# STM32F103C8T6.net
KiCad netlist of a schematic drawn in EasyEDA Pro
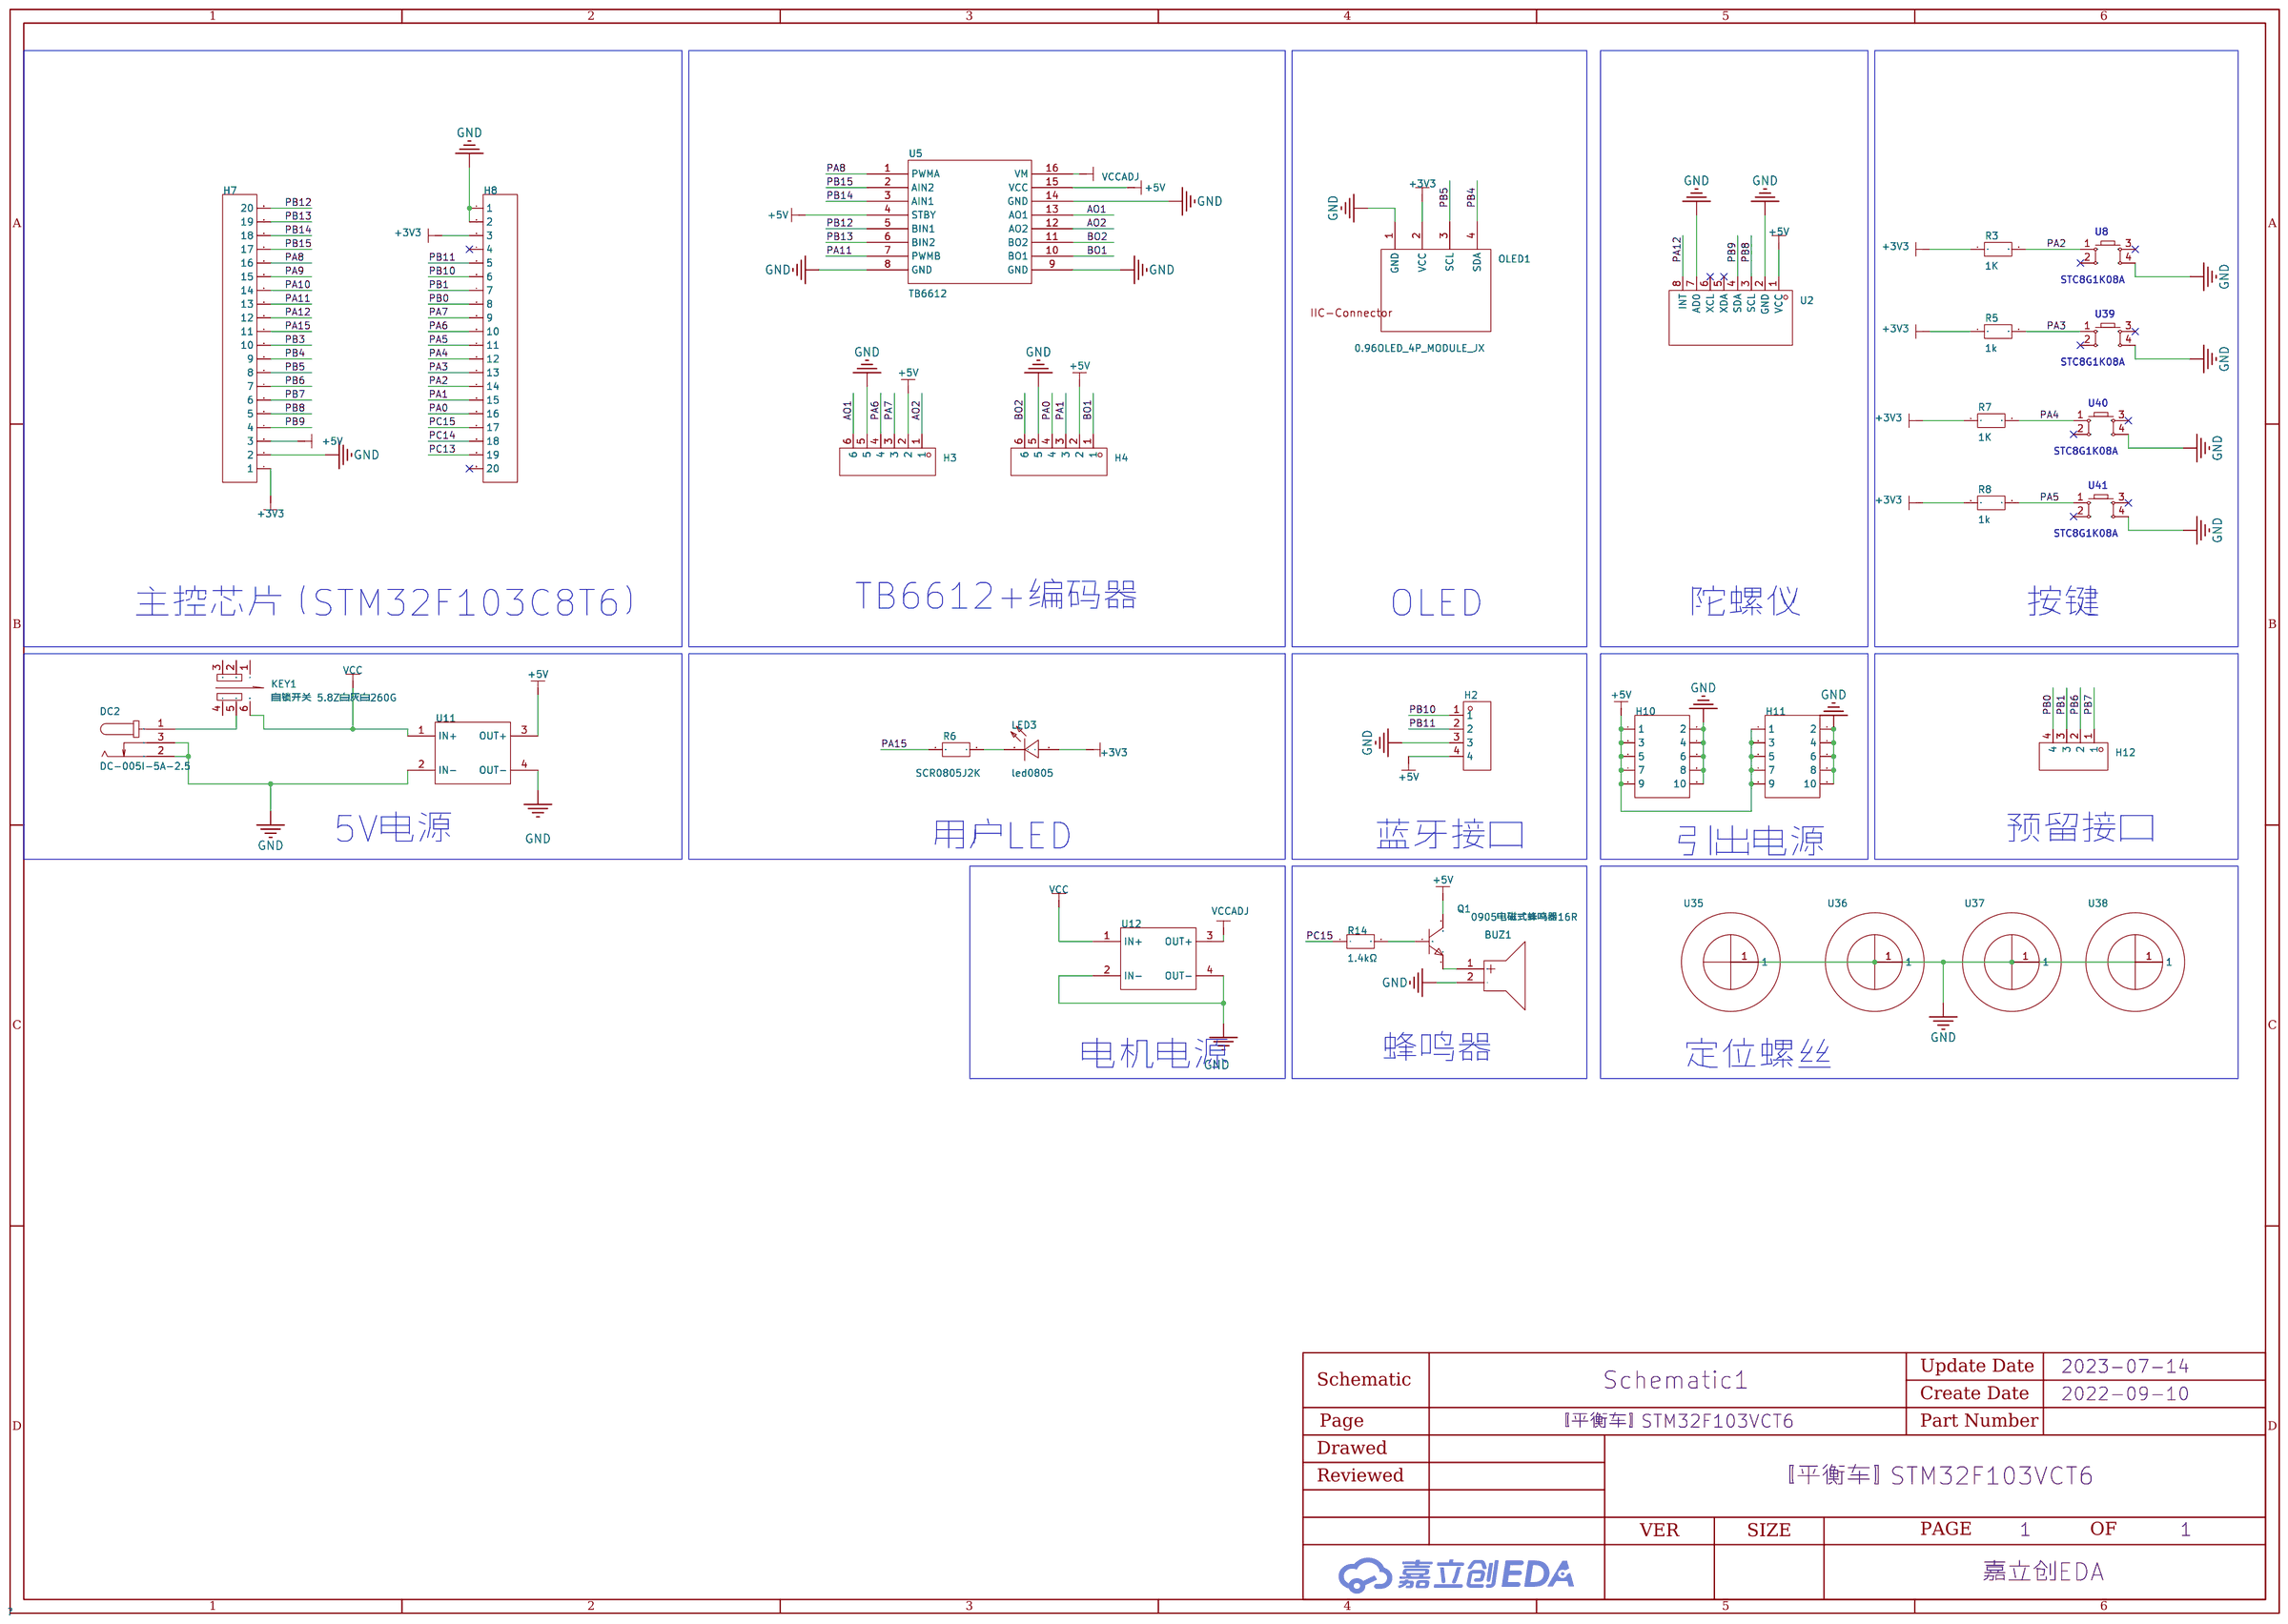
[diagram p0: schematic sheet]

(export (version "E")
  (design (tool "Eeschema 10.0.6"))
  (components
    (comp (ref "BUZ1")
      (value "0905电磁式蜂鸣器16R")
      (footprint "easyedapro:BUZ-TH_BD9.0-P4.00-D0.6-FD")
      (libsource (lib "easyedapro") (part "0905电磁式蜂鸣器16R"))
    )
    (comp (ref "DC2")
      (value "DC-005I-5A-2.5")
      (footprint "easyedapro:DC-IN-TH_DC-005I-5A-2.5")
      (fields (field (name "Manufacturer") "XKB Connectivity(中国星坤)"))
      (libsource (lib "easyedapro") (part "DC-005I-5A-2.5"))
    )
    (comp (ref "H2")
      (value "~")
      (footprint "easyedapro:HDR-TH_4P-P2.54-V-F")
      (libsource (lib "easyedapro") (part "2.54-1*4P母"))
    )
    (comp (ref "H3")
      (value "~")
      (footprint "easyedapro:HDR-TH_6P-P2.54-V-F")
      (libsource (lib "easyedapro") (part "Header-Female-2.54_1x6"))
    )
    (comp (ref "H4")
      (value "~")
      (footprint "easyedapro:HDR-TH_6P-P2.54-V-F")
      (libsource (lib "easyedapro") (part "Header-Female-2.54_1x6"))
    )
    (comp (ref "H7")
      (value "~")
      (footprint "easyedapro:HDR-TH_20P-P2.54-V-F")
      (libsource (lib "easyedapro") (part "HDR-F_2.54_1x20P"))
    )
    (comp (ref "H8")
      (value "~")
      (footprint "easyedapro:HDR-TH_20P-P2.54-V-F")
      (libsource (lib "easyedapro") (part "HDR-F_2.54_1x20P"))
    )
    (comp (ref "H10")
      (value "~")
      (footprint "easyedapro:HDR-TH_10P-P2.54-V-F-R2-C5-S2.54")
      (libsource (lib "easyedapro") (part "HDR-F-2.54_2x5"))
    )
    (comp (ref "H11")
      (value "~")
      (footprint "easyedapro:HDR-TH_10P-P2.54-V-F-R2-C5-S2.54")
      (libsource (lib "easyedapro") (part "HDR-F-2.54_2x5"))
    )
    (comp (ref "H12")
      (value "~")
      (footprint "easyedapro:HDR-TH_4P-P2.54-V-F")
      (libsource (lib "easyedapro") (part "2.54-1*4P母"))
    )
    (comp (ref "KEY1")
      (value "自锁开关 5.8Z白灰白260G")
      (footprint "easyedapro:SW-TH_6P-L5.8-W5.8-P2.00-LS4.5-TR")
      (description "耐温260度")
      (libsource (lib "easyedapro") (part "Self-locking switch 5.8ZWhite and white260G"))
    )
    (comp (ref "LED3")
      (value "led0805")
      (footprint "easyedapro:LED0805-RD")
      (libsource (lib "easyedapro") (part "LED0805"))
    )
    (comp (ref "OLED1")
      (value "0.96OLED_4P_MODULE_JX")
      (footprint "easyedapro:0.96OLED_4P")
      (libsource (lib "easyedapro") (part "0.96OLED_4P_MODULE_JX"))
    )
    (comp (ref "Q1")
      (value "~")
      (footprint "easyedapro:S8050_TO_92")
      (libsource (lib "easyedapro") (part "S8050_TO_NPN"))
    )
    (comp (ref "R3")
      (value "1K")
      (footprint "easyedapro:R0805")
      (fields (field (name "Manufacturer Part") "SCR0805J2K") (field (name "Manufacturer") "VO(翔胜)"))
      (libsource (lib "easyedapro") (part "SCR0805J2K"))
    )
    (comp (ref "R5")
      (value "1k")
      (footprint "easyedapro:R0805")
      (fields (field (name "Manufacturer Part") "SCR0805J2K") (field (name "Manufacturer") "VO(翔胜)"))
      (libsource (lib "easyedapro") (part "SCR0805J2K"))
    )
    (comp (ref "R6")
      (value "SCR0805J2K")
      (footprint "easyedapro:R0805")
      (fields (field (name "Manufacturer") "VO(翔胜)"))
      (libsource (lib "easyedapro") (part "SCR0805J2K"))
    )
    (comp (ref "R7")
      (value "1K")
      (footprint "easyedapro:R0805")
      (fields (field (name "Manufacturer Part") "SCR0805J2K") (field (name "Manufacturer") "VO(翔胜)"))
      (libsource (lib "easyedapro") (part "SCR0805J2K"))
    )
    (comp (ref "R8")
      (value "1k")
      (footprint "easyedapro:R0805")
      (fields (field (name "Manufacturer Part") "SCR0805J2K") (field (name "Manufacturer") "VO(翔胜)"))
      (libsource (lib "easyedapro") (part "SCR0805J2K"))
    )
    (comp (ref "R14")
      (value "1.4kΩ")
      (footprint "easyedapro:R0603")
      (description "电阻类型:厚膜电阻;阻值:1.4kΩ;精度:±1%;功率:100mW;")
      (fields
        (field (name "Manufacturer Part") "CRCW06031K40FKEA")
        (field (name "Manufacturer") "VISHAY(威世)")
      )
      (libsource (lib "easyedapro") (part "CRCW06031K40FKEA"))
    )
    (comp (ref "U2")
      (value "~")
      (footprint "easyedapro:MPU6050")
      (libsource (lib "easyedapro") (part "MPU6050"))
    )
    (comp (ref "U5")
      (value "TB6612")
      (footprint "easyedapro:TB6612")
      (libsource (lib "easyedapro") (part "TB6612"))
    )
    (comp (ref "U8")
      (value "STC8G1K08A")
      (footprint "easyedapro:SW-TH_4P-L6.0-W6.0-P4.50-LS6.5")
      (libsource (lib "easyedapro") (part "轻触按键直插"))
    )
    (comp (ref "U11")
      (value "~")
      (footprint "easyedapro:LM2596模块")
      (libsource (lib "easyedapro") (part "LM2596模块"))
    )
    (comp (ref "U12")
      (value "~")
      (footprint "easyedapro:LM2596模块")
      (libsource (lib "easyedapro") (part "LM2596模块"))
    )
    (comp (ref "U35")
      (value "~")
      (footprint "easyedapro:M3_花孔")
      (libsource (lib "easyedapro") (part "M3孔_花孔"))
    )
    (comp (ref "U36")
      (value "~")
      (footprint "easyedapro:M3_花孔")
      (libsource (lib "easyedapro") (part "M3孔_花孔"))
    )
    (comp (ref "U37")
      (value "~")
      (footprint "easyedapro:M3_花孔")
      (libsource (lib "easyedapro") (part "M3孔_花孔"))
    )
    (comp (ref "U38")
      (value "~")
      (footprint "easyedapro:M3_花孔")
      (libsource (lib "easyedapro") (part "M3孔_花孔"))
    )
    (comp (ref "U39")
      (value "STC8G1K08A")
      (footprint "easyedapro:SW-TH_4P-L6.0-W6.0-P4.50-LS6.5")
      (libsource (lib "easyedapro") (part "轻触按键直插"))
    )
    (comp (ref "U40")
      (value "STC8G1K08A")
      (footprint "easyedapro:SW-TH_4P-L6.0-W6.0-P4.50-LS6.5")
      (libsource (lib "easyedapro") (part "轻触按键直插"))
    )
    (comp (ref "U41")
      (value "STC8G1K08A")
      (footprint "easyedapro:SW-TH_4P-L6.0-W6.0-P4.50-LS6.5")
      (libsource (lib "easyedapro") (part "轻触按键直插"))
    )
  )
  (nets
    (net (code "1") (name "+3V3") (class "Default")
      (node (ref "H7") (pin "1") (pinfunction "1_1") (pintype "input"))
      (node (ref "H8") (pin "3") (pinfunction "3_3") (pintype "input"))
      (node (ref "LED3") (pin "2") (pinfunction "+_2") (pintype "input"))
      (node (ref "OLED1") (pin "2") (pinfunction "VCC_2") (pintype "input"))
      (node (ref "R3") (pin "1") (pinfunction "1_1") (pintype "input"))
      (node (ref "R5") (pin "1") (pinfunction "1_1") (pintype "input"))
      (node (ref "R7") (pin "1") (pinfunction "1_1") (pintype "input"))
      (node (ref "R8") (pin "1") (pinfunction "1_1") (pintype "input"))
    )
    (net (code "2") (name "+5V") (class "Default")
      (node (ref "H10") (pin "1") (pinfunction "1_1") (pintype "input"))
      (node (ref "H10") (pin "3") (pinfunction "3_3") (pintype "input"))
      (node (ref "H10") (pin "5") (pinfunction "5_5") (pintype "input"))
      (node (ref "H10") (pin "7") (pinfunction "7_7") (pintype "input"))
      (node (ref "H10") (pin "9") (pinfunction "9_9") (pintype "input"))
      (node (ref "H11") (pin "1") (pinfunction "1_1") (pintype "input"))
      (node (ref "H11") (pin "3") (pinfunction "3_3") (pintype "input"))
      (node (ref "H11") (pin "5") (pinfunction "5_5") (pintype "input"))
      (node (ref "H11") (pin "7") (pinfunction "7_7") (pintype "input"))
      (node (ref "H11") (pin "9") (pinfunction "9_9") (pintype "input"))
      (node (ref "H2") (pin "4") (pinfunction "4_4") (pintype "input"))
      (node (ref "H3") (pin "2") (pinfunction "2_2") (pintype "input"))
      (node (ref "H4") (pin "2") (pinfunction "2_2") (pintype "input"))
      (node (ref "H7") (pin "3") (pinfunction "3_3") (pintype "input"))
      (node (ref "Q1") (pin "3") (pinfunction "C_3") (pintype "unspecified"))
      (node (ref "U11") (pin "3") (pinfunction "OUT+_3") (pintype "input"))
      (node (ref "U2") (pin "1") (pinfunction "VCC_1") (pintype "input"))
      (node (ref "U5") (pin "15") (pinfunction "VCC_15") (pintype "input"))
      (node (ref "U5") (pin "4") (pinfunction "STBY_4") (pintype "input"))
    )
    (net (code "3") (name "/AO1") (class "Default")
      (node (ref "H3") (pin "6") (pinfunction "6_6") (pintype "input"))
      (node (ref "U5") (pin "13") (pinfunction "AO1_13") (pintype "input"))
    )
    (net (code "4") (name "/AO2") (class "Default")
      (node (ref "H3") (pin "1") (pinfunction "1_1") (pintype "input"))
      (node (ref "U5") (pin "12") (pinfunction "AO2_12") (pintype "input"))
    )
    (net (code "5") (name "/BO1") (class "Default")
      (node (ref "H4") (pin "1") (pinfunction "1_1") (pintype "input"))
      (node (ref "U5") (pin "10") (pinfunction "BO1_10") (pintype "input"))
    )
    (net (code "6") (name "/BO2") (class "Default")
      (node (ref "H4") (pin "6") (pinfunction "6_6") (pintype "input"))
      (node (ref "U5") (pin "11") (pinfunction "BO2_11") (pintype "input"))
    )
    (net (code "7") (name "/PA0") (class "Default")
      (node (ref "H4") (pin "4") (pinfunction "4_4") (pintype "input"))
      (node (ref "H8") (pin "16") (pinfunction "16_16") (pintype "input"))
    )
    (net (code "8") (name "/PA1") (class "Default")
      (node (ref "H4") (pin "3") (pinfunction "3_3") (pintype "input"))
      (node (ref "H8") (pin "15") (pinfunction "15_15") (pintype "input"))
    )
    (net (code "9") (name "/PA2") (class "Default")
      (node (ref "H8") (pin "14") (pinfunction "14_14") (pintype "input"))
      (node (ref "R3") (pin "2") (pinfunction "2_2") (pintype "input"))
      (node (ref "U8") (pin "1") (pinfunction "1_1") (pintype "input"))
    )
    (net (code "10") (name "/PA3") (class "Default")
      (node (ref "H8") (pin "13") (pinfunction "13_13") (pintype "input"))
      (node (ref "R5") (pin "2") (pinfunction "2_2") (pintype "input"))
      (node (ref "U39") (pin "1") (pinfunction "1_1") (pintype "input"))
    )
    (net (code "11") (name "/PA4") (class "Default")
      (node (ref "H8") (pin "12") (pinfunction "12_12") (pintype "input"))
      (node (ref "R7") (pin "2") (pinfunction "2_2") (pintype "input"))
      (node (ref "U40") (pin "1") (pinfunction "1_1") (pintype "input"))
    )
    (net (code "12") (name "/PA5") (class "Default")
      (node (ref "H8") (pin "11") (pinfunction "11_11") (pintype "input"))
      (node (ref "R8") (pin "2") (pinfunction "2_2") (pintype "input"))
      (node (ref "U41") (pin "1") (pinfunction "1_1") (pintype "input"))
    )
    (net (code "13") (name "/PA6") (class "Default")
      (node (ref "H3") (pin "4") (pinfunction "4_4") (pintype "input"))
      (node (ref "H8") (pin "10") (pinfunction "10_10") (pintype "input"))
    )
    (net (code "14") (name "/PA7") (class "Default")
      (node (ref "H3") (pin "3") (pinfunction "3_3") (pintype "input"))
      (node (ref "H8") (pin "9") (pinfunction "9_9") (pintype "input"))
    )
    (net (code "15") (name "/PA8") (class "Default")
      (node (ref "H7") (pin "16") (pinfunction "16_16") (pintype "input"))
      (node (ref "U5") (pin "1") (pinfunction "PWMA_1") (pintype "input"))
    )
    (net (code "16") (name "/PA9") (class "Default")
      (node (ref "H7") (pin "15") (pinfunction "15_15") (pintype "input"))
    )
    (net (code "17") (name "/PA10") (class "Default")
      (node (ref "H7") (pin "14") (pinfunction "14_14") (pintype "input"))
    )
    (net (code "18") (name "/PA11") (class "Default")
      (node (ref "H7") (pin "13") (pinfunction "13_13") (pintype "input"))
      (node (ref "U5") (pin "7") (pinfunction "PWMB_7") (pintype "input"))
    )
    (net (code "19") (name "/PA12") (class "Default")
      (node (ref "H7") (pin "12") (pinfunction "12_12") (pintype "input"))
      (node (ref "U2") (pin "8") (pinfunction "INT_8") (pintype "input"))
    )
    (net (code "20") (name "/PA15") (class "Default")
      (node (ref "H7") (pin "11") (pinfunction "11_11") (pintype "input"))
      (node (ref "R6") (pin "1") (pinfunction "1_1") (pintype "input"))
    )
    (net (code "21") (name "/PB0") (class "Default")
      (node (ref "H12") (pin "4") (pinfunction "4_4") (pintype "input"))
      (node (ref "H8") (pin "8") (pinfunction "8_8") (pintype "input"))
    )
    (net (code "22") (name "/PB1") (class "Default")
      (node (ref "H12") (pin "3") (pinfunction "3_3") (pintype "input"))
      (node (ref "H8") (pin "7") (pinfunction "7_7") (pintype "input"))
    )
    (net (code "23") (name "/PB3") (class "Default")
      (node (ref "H7") (pin "10") (pinfunction "10_10") (pintype "input"))
    )
    (net (code "24") (name "/PB4") (class "Default")
      (node (ref "H7") (pin "9") (pinfunction "9_9") (pintype "input"))
      (node (ref "OLED1") (pin "4") (pinfunction "SDA_4") (pintype "input"))
    )
    (net (code "25") (name "/PB5") (class "Default")
      (node (ref "H7") (pin "8") (pinfunction "8_8") (pintype "input"))
      (node (ref "OLED1") (pin "3") (pinfunction "SCL_3") (pintype "input"))
    )
    (net (code "26") (name "/PB6") (class "Default")
      (node (ref "H12") (pin "2") (pinfunction "2_2") (pintype "input"))
      (node (ref "H7") (pin "7") (pinfunction "7_7") (pintype "input"))
    )
    (net (code "27") (name "/PB7") (class "Default")
      (node (ref "H12") (pin "1") (pinfunction "1_1") (pintype "input"))
      (node (ref "H7") (pin "6") (pinfunction "6_6") (pintype "input"))
    )
    (net (code "28") (name "/PB8") (class "Default")
      (node (ref "H7") (pin "5") (pinfunction "5_5") (pintype "input"))
      (node (ref "U2") (pin "3") (pinfunction "SCL_3") (pintype "input"))
    )
    (net (code "29") (name "/PB9") (class "Default")
      (node (ref "H7") (pin "4") (pinfunction "4_4") (pintype "input"))
      (node (ref "U2") (pin "4") (pinfunction "SDA_4") (pintype "input"))
    )
    (net (code "30") (name "/PB10") (class "Default")
      (node (ref "H2") (pin "1") (pinfunction "1_1") (pintype "input"))
      (node (ref "H8") (pin "6") (pinfunction "6_6") (pintype "input"))
    )
    (net (code "31") (name "/PB11") (class "Default")
      (node (ref "H2") (pin "2") (pinfunction "2_2") (pintype "input"))
      (node (ref "H8") (pin "5") (pinfunction "5_5") (pintype "input"))
    )
    (net (code "32") (name "/PB12") (class "Default")
      (node (ref "H7") (pin "20") (pinfunction "20_20") (pintype "input"))
      (node (ref "U5") (pin "5") (pinfunction "BIN1_5") (pintype "input"))
    )
    (net (code "33") (name "/PB13") (class "Default")
      (node (ref "H7") (pin "19") (pinfunction "19_19") (pintype "input"))
      (node (ref "U5") (pin "6") (pinfunction "BIN2_6") (pintype "input"))
    )
    (net (code "34") (name "/PB14") (class "Default")
      (node (ref "H7") (pin "18") (pinfunction "18_18") (pintype "input"))
      (node (ref "U5") (pin "3") (pinfunction "AIN1_3") (pintype "input"))
    )
    (net (code "35") (name "/PB15") (class "Default")
      (node (ref "H7") (pin "17") (pinfunction "17_17") (pintype "input"))
      (node (ref "U5") (pin "2") (pinfunction "AIN2_2") (pintype "input"))
    )
    (net (code "36") (name "/PC13") (class "Default")
      (node (ref "H8") (pin "19") (pinfunction "19_19") (pintype "input"))
    )
    (net (code "37") (name "/PC14") (class "Default")
      (node (ref "H8") (pin "18") (pinfunction "18_18") (pintype "input"))
    )
    (net (code "38") (name "/PC15") (class "Default")
      (node (ref "H8") (pin "17") (pinfunction "17_17") (pintype "input"))
      (node (ref "R14") (pin "1") (pinfunction "1_1") (pintype "input"))
    )
    (net (code "39") (name "GND") (class "Default")
      (node (ref "BUZ1") (pin "2") (pinfunction "-_2") (pintype "input"))
      (node (ref "DC2") (pin "2") (pinfunction "2_2") (pintype "input"))
      (node (ref "DC2") (pin "3") (pinfunction "3_3") (pintype "input"))
      (node (ref "H10") (pin "10") (pinfunction "10_10") (pintype "input"))
      (node (ref "H10") (pin "2") (pinfunction "2_2") (pintype "input"))
      (node (ref "H10") (pin "4") (pinfunction "4_4") (pintype "input"))
      (node (ref "H10") (pin "6") (pinfunction "6_6") (pintype "input"))
      (node (ref "H10") (pin "8") (pinfunction "8_8") (pintype "input"))
      (node (ref "H11") (pin "10") (pinfunction "10_10") (pintype "input"))
      (node (ref "H11") (pin "2") (pinfunction "2_2") (pintype "input"))
      (node (ref "H11") (pin "4") (pinfunction "4_4") (pintype "input"))
      (node (ref "H11") (pin "6") (pinfunction "6_6") (pintype "input"))
      (node (ref "H11") (pin "8") (pinfunction "8_8") (pintype "input"))
      (node (ref "H2") (pin "3") (pinfunction "3_3") (pintype "input"))
      (node (ref "H3") (pin "5") (pinfunction "5_5") (pintype "input"))
      (node (ref "H4") (pin "5") (pinfunction "5_5") (pintype "input"))
      (node (ref "H7") (pin "2") (pinfunction "2_2") (pintype "input"))
      (node (ref "H8") (pin "1") (pinfunction "1_1") (pintype "input"))
      (node (ref "H8") (pin "2") (pinfunction "2_2") (pintype "input"))
      (node (ref "OLED1") (pin "1") (pinfunction "GND_1") (pintype "input"))
      (node (ref "U11") (pin "2") (pinfunction "IN-_2") (pintype "input"))
      (node (ref "U11") (pin "4") (pinfunction "OUT-_4") (pintype "input"))
      (node (ref "U12") (pin "2") (pinfunction "IN-_2") (pintype "input"))
      (node (ref "U12") (pin "4") (pinfunction "OUT-_4") (pintype "input"))
      (node (ref "U2") (pin "2") (pinfunction "GND_2") (pintype "input"))
      (node (ref "U2") (pin "7") (pinfunction "AD0_7") (pintype "input"))
      (node (ref "U35") (pin "1") (pinfunction "1_1") (pintype "input"))
      (node (ref "U36") (pin "1") (pinfunction "1_1") (pintype "input"))
      (node (ref "U37") (pin "1") (pinfunction "1_1") (pintype "input"))
      (node (ref "U38") (pin "1") (pinfunction "1_1") (pintype "input"))
      (node (ref "U39") (pin "4") (pinfunction "4_4") (pintype "input"))
      (node (ref "U40") (pin "4") (pinfunction "4_4") (pintype "input"))
      (node (ref "U41") (pin "4") (pinfunction "4_4") (pintype "input"))
      (node (ref "U5") (pin "14") (pinfunction "GND_14") (pintype "input"))
      (node (ref "U5") (pin "8") (pinfunction "GND_8") (pintype "input"))
      (node (ref "U5") (pin "9") (pinfunction "GND_9") (pintype "input"))
      (node (ref "U8") (pin "4") (pinfunction "4_4") (pintype "input"))
    )
    (net (code "40") (name "Net-(BUZ1-+)") (class "Default")
      (node (ref "BUZ1") (pin "1") (pinfunction "+_1") (pintype "input"))
      (node (ref "Q1") (pin "1") (pinfunction "E_1") (pintype "unspecified"))
    )
    (net (code "41") (name "Net-(DC2-Pad1)") (class "Default")
      (node (ref "DC2") (pin "1") (pinfunction "1_1") (pintype "input"))
      (node (ref "KEY1") (pin "5") (pinfunction "5_5") (pintype "input"))
    )
    (net (code "42") (name "Net-(LED3--)") (class "Default")
      (node (ref "LED3") (pin "1") (pinfunction "-_1") (pintype "input"))
      (node (ref "R6") (pin "2") (pinfunction "2_2") (pintype "input"))
    )
    (net (code "43") (name "Net-(Q1-B)") (class "Default")
      (node (ref "Q1") (pin "2") (pinfunction "B_2") (pintype "unspecified"))
      (node (ref "R14") (pin "2") (pinfunction "2_2") (pintype "input"))
    )
    (net (code "44") (name "VCC") (class "Default")
      (node (ref "KEY1") (pin "6") (pinfunction "6_6") (pintype "input"))
      (node (ref "U11") (pin "1") (pinfunction "IN+_1") (pintype "input"))
      (node (ref "U12") (pin "1") (pinfunction "IN+_1") (pintype "input"))
    )
    (net (code "45") (name "VCCADJ") (class "Default")
      (node (ref "U12") (pin "3") (pinfunction "OUT+_3") (pintype "input"))
      (node (ref "U5") (pin "16") (pinfunction "VM_16") (pintype "input"))
    )
    (net (code "46") (name "unconnected-(H8-Pad4)") (class "Default")
      (node (ref "H8") (pin "4") (pinfunction "4_4") (pintype "input+no_connect"))
    )
    (net (code "47") (name "unconnected-(H8-Pad20)") (class "Default")
      (node (ref "H8") (pin "20") (pinfunction "20_20") (pintype "input+no_connect"))
    )
    (net (code "48") (name "unconnected-(KEY1-Pad1)") (class "Default")
      (node (ref "KEY1") (pin "1") (pinfunction "1_1") (pintype "input"))
    )
    (net (code "49") (name "unconnected-(KEY1-Pad2)") (class "Default")
      (node (ref "KEY1") (pin "2") (pinfunction "2_2") (pintype "input"))
    )
    (net (code "50") (name "unconnected-(KEY1-Pad3)") (class "Default")
      (node (ref "KEY1") (pin "3") (pinfunction "3_3") (pintype "input"))
    )
    (net (code "51") (name "unconnected-(KEY1-Pad4)") (class "Default")
      (node (ref "KEY1") (pin "4") (pinfunction "4_4") (pintype "input"))
    )
    (net (code "52") (name "unconnected-(U2-XCL-Pad6)") (class "Default")
      (node (ref "U2") (pin "6") (pinfunction "XCL_6") (pintype "input+no_connect"))
    )
    (net (code "53") (name "unconnected-(U2-XDA-Pad5)") (class "Default")
      (node (ref "U2") (pin "5") (pinfunction "XDA_5") (pintype "input+no_connect"))
    )
    (net (code "54") (name "unconnected-(U8-Pad2)") (class "Default")
      (node (ref "U8") (pin "2") (pinfunction "2_2") (pintype "input+no_connect"))
    )
    (net (code "55") (name "unconnected-(U8-Pad3)") (class "Default")
      (node (ref "U8") (pin "3") (pinfunction "3_3") (pintype "input+no_connect"))
    )
    (net (code "56") (name "unconnected-(U39-Pad2)") (class "Default")
      (node (ref "U39") (pin "2") (pinfunction "2_2") (pintype "input+no_connect"))
    )
    (net (code "57") (name "unconnected-(U39-Pad3)") (class "Default")
      (node (ref "U39") (pin "3") (pinfunction "3_3") (pintype "input+no_connect"))
    )
    (net (code "58") (name "unconnected-(U40-Pad2)") (class "Default")
      (node (ref "U40") (pin "2") (pinfunction "2_2") (pintype "input+no_connect"))
    )
    (net (code "59") (name "unconnected-(U40-Pad3)") (class "Default")
      (node (ref "U40") (pin "3") (pinfunction "3_3") (pintype "input+no_connect"))
    )
    (net (code "60") (name "unconnected-(U41-Pad2)") (class "Default")
      (node (ref "U41") (pin "2") (pinfunction "2_2") (pintype "input+no_connect"))
    )
    (net (code "61") (name "unconnected-(U41-Pad3)") (class "Default")
      (node (ref "U41") (pin "3") (pinfunction "3_3") (pintype "input+no_connect"))
    )
  )
)
